# gpio_tcal9539_expander.net
KiCad netlist of a schematic drawn in Altium Designer
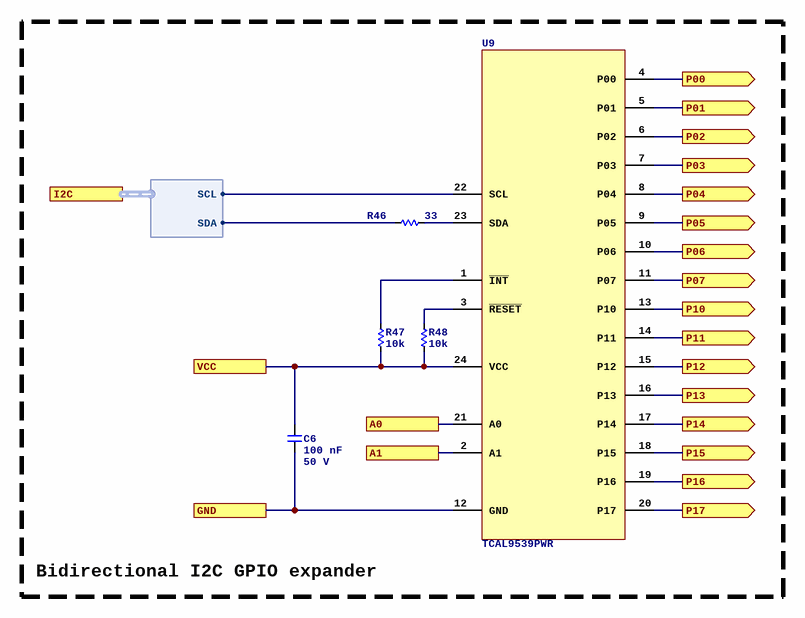
[diagram p0: gpio_tcal9539_expander.SchDoc]

(export (version "E")
  (design (tool "Eeschema 10.0.6"))
  (components
    (comp (ref "C6")
      (value "CL05B104KB54PNC")
      (footprint "C0402")
      (fields
        (field (name "CAPACITANCE") "100 nF")
        (field (name "MANUFACTURER") "Samsung Electro-Mechanics")
        (field (name "VOLTAGE RATING") "50 V")
      )
      (libsource (lib "database") (part "__template_cap"))
    )
    (comp (ref "R46")
      (value "33")
      (footprint "R0402")
      (fields
        (field (name "TOLERANCE") "1%")
        (field (name "MANUFACTURER PART NUMBER") "CRCW040233R0FKED")
        (field (name "MANUFACTURER") "Vishay Intertech")
      )
      (libsource (lib "database") (part "__template_resistor"))
    )
    (comp (ref "R47")
      (value "10k")
      (footprint "R0402")
      (fields
        (field (name "TOLERANCE") "1%")
        (field (name "MANUFACTURER PART NUMBER") "0402WGF1002TCE")
        (field (name "MANUFACTURER") "UNI-ROYAL(Uniroyal Elec)")
      )
      (libsource (lib "database") (part "__template_resistor"))
    )
    (comp (ref "R48")
      (value "10k")
      (footprint "R0402")
      (fields
        (field (name "TOLERANCE") "1%")
        (field (name "MANUFACTURER PART NUMBER") "0402WGF1002TCE")
        (field (name "MANUFACTURER") "UNI-ROYAL(Uniroyal Elec)")
      )
      (libsource (lib "database") (part "__template_resistor"))
    )
    (comp (ref "U9")
      (value "TCAL9539PWR")
      (footprint "24TSSOP65")
      (description "I/O Expander 16 I2C, SMBus 1 MHz 24-TSSOP")
      (fields (field (name "MANUFACTURER") "Texas Instruments"))
      (libsource (lib "database") (part "TCAL9539PWR"))
    )
  )
  (nets
    (net (code "2") (name "/A0") (class "Default")
      (node (ref "U9") (pin "21") (pinfunction "A0_21") (pintype "passive"))
    )
    (net (code "3") (name "/A1") (class "Default")
      (node (ref "U9") (pin "2") (pinfunction "A1_2") (pintype "passive"))
    )
    (net (code "4") (name "/GND") (class "Default")
      (node (ref "C6") (pin "2") (pintype "passive"))
      (node (ref "U9") (pin "12") (pinfunction "GND_12") (pintype "passive"))
    )
    (net (code "5") (name "/P00") (class "Default")
      (node (ref "U9") (pin "4") (pinfunction "P00_4") (pintype "passive"))
    )
    (net (code "6") (name "/P01") (class "Default")
      (node (ref "U9") (pin "5") (pinfunction "P01_5") (pintype "passive"))
    )
    (net (code "7") (name "/P02") (class "Default")
      (node (ref "U9") (pin "6") (pinfunction "P02_6") (pintype "passive"))
    )
    (net (code "8") (name "/P03") (class "Default")
      (node (ref "U9") (pin "7") (pinfunction "P03_7") (pintype "passive"))
    )
    (net (code "9") (name "/P04") (class "Default")
      (node (ref "U9") (pin "8") (pinfunction "P04_8") (pintype "passive"))
    )
    (net (code "10") (name "/P05") (class "Default")
      (node (ref "U9") (pin "9") (pinfunction "P05_9") (pintype "passive"))
    )
    (net (code "11") (name "/P06") (class "Default")
      (node (ref "U9") (pin "10") (pinfunction "P06_10") (pintype "passive"))
    )
    (net (code "12") (name "/P07") (class "Default")
      (node (ref "U9") (pin "11") (pinfunction "P07_11") (pintype "passive"))
    )
    (net (code "13") (name "/P10") (class "Default")
      (node (ref "U9") (pin "13") (pinfunction "P10_13") (pintype "passive"))
    )
    (net (code "14") (name "/P11") (class "Default")
      (node (ref "U9") (pin "14") (pinfunction "P11_14") (pintype "passive"))
    )
    (net (code "15") (name "/P12") (class "Default")
      (node (ref "U9") (pin "15") (pinfunction "P12_15") (pintype "passive"))
    )
    (net (code "16") (name "/P13") (class "Default")
      (node (ref "U9") (pin "16") (pinfunction "P13_16") (pintype "passive"))
    )
    (net (code "17") (name "/P14") (class "Default")
      (node (ref "U9") (pin "17") (pinfunction "P14_17") (pintype "passive"))
    )
    (net (code "18") (name "/P15") (class "Default")
      (node (ref "U9") (pin "18") (pinfunction "P15_18") (pintype "passive"))
    )
    (net (code "19") (name "/P16") (class "Default")
      (node (ref "U9") (pin "19") (pinfunction "P16_19") (pintype "passive"))
    )
    (net (code "20") (name "/P17") (class "Default")
      (node (ref "U9") (pin "20") (pinfunction "P17_20") (pintype "passive"))
    )
    (net (code "21") (name "/SCL") (class "Default")
      (node (ref "U9") (pin "22") (pinfunction "SCL_22") (pintype "passive"))
    )
    (net (code "22") (name "/SDA") (class "Default") (node (ref "R46") (pin "2") (pintype "passive")))
    (net (code "23") (name "/VCC") (class "Default")
      (node (ref "C6") (pin "1") (pintype "passive"))
      (node (ref "R47") (pin "1") (pintype "passive"))
      (node (ref "R48") (pin "1") (pintype "passive"))
      (node (ref "U9") (pin "24") (pinfunction "VCC_24") (pintype "passive"))
    )
    (net (code "25") (name "Net-(U9-SDA)") (class "Default")
      (node (ref "R46") (pin "1") (pintype "passive"))
      (node (ref "U9") (pin "23") (pinfunction "SDA_23") (pintype "passive"))
    )
    (net (code "26") (name "Net-(U9-~{INT})") (class "Default")
      (node (ref "R47") (pin "2") (pintype "passive"))
      (node (ref "U9") (pin "1") (pinfunction "~{INT}_1") (pintype "passive"))
    )
    (net (code "27") (name "Net-(U9-~{RESET})") (class "Default")
      (node (ref "R48") (pin "2") (pintype "passive"))
      (node (ref "U9") (pin "3") (pinfunction "~{RESET}_3") (pintype "passive"))
    )
  )
)
